# Wordwatch_-_complete.net
KiCad netlist of a schematic drawn in EAGLE
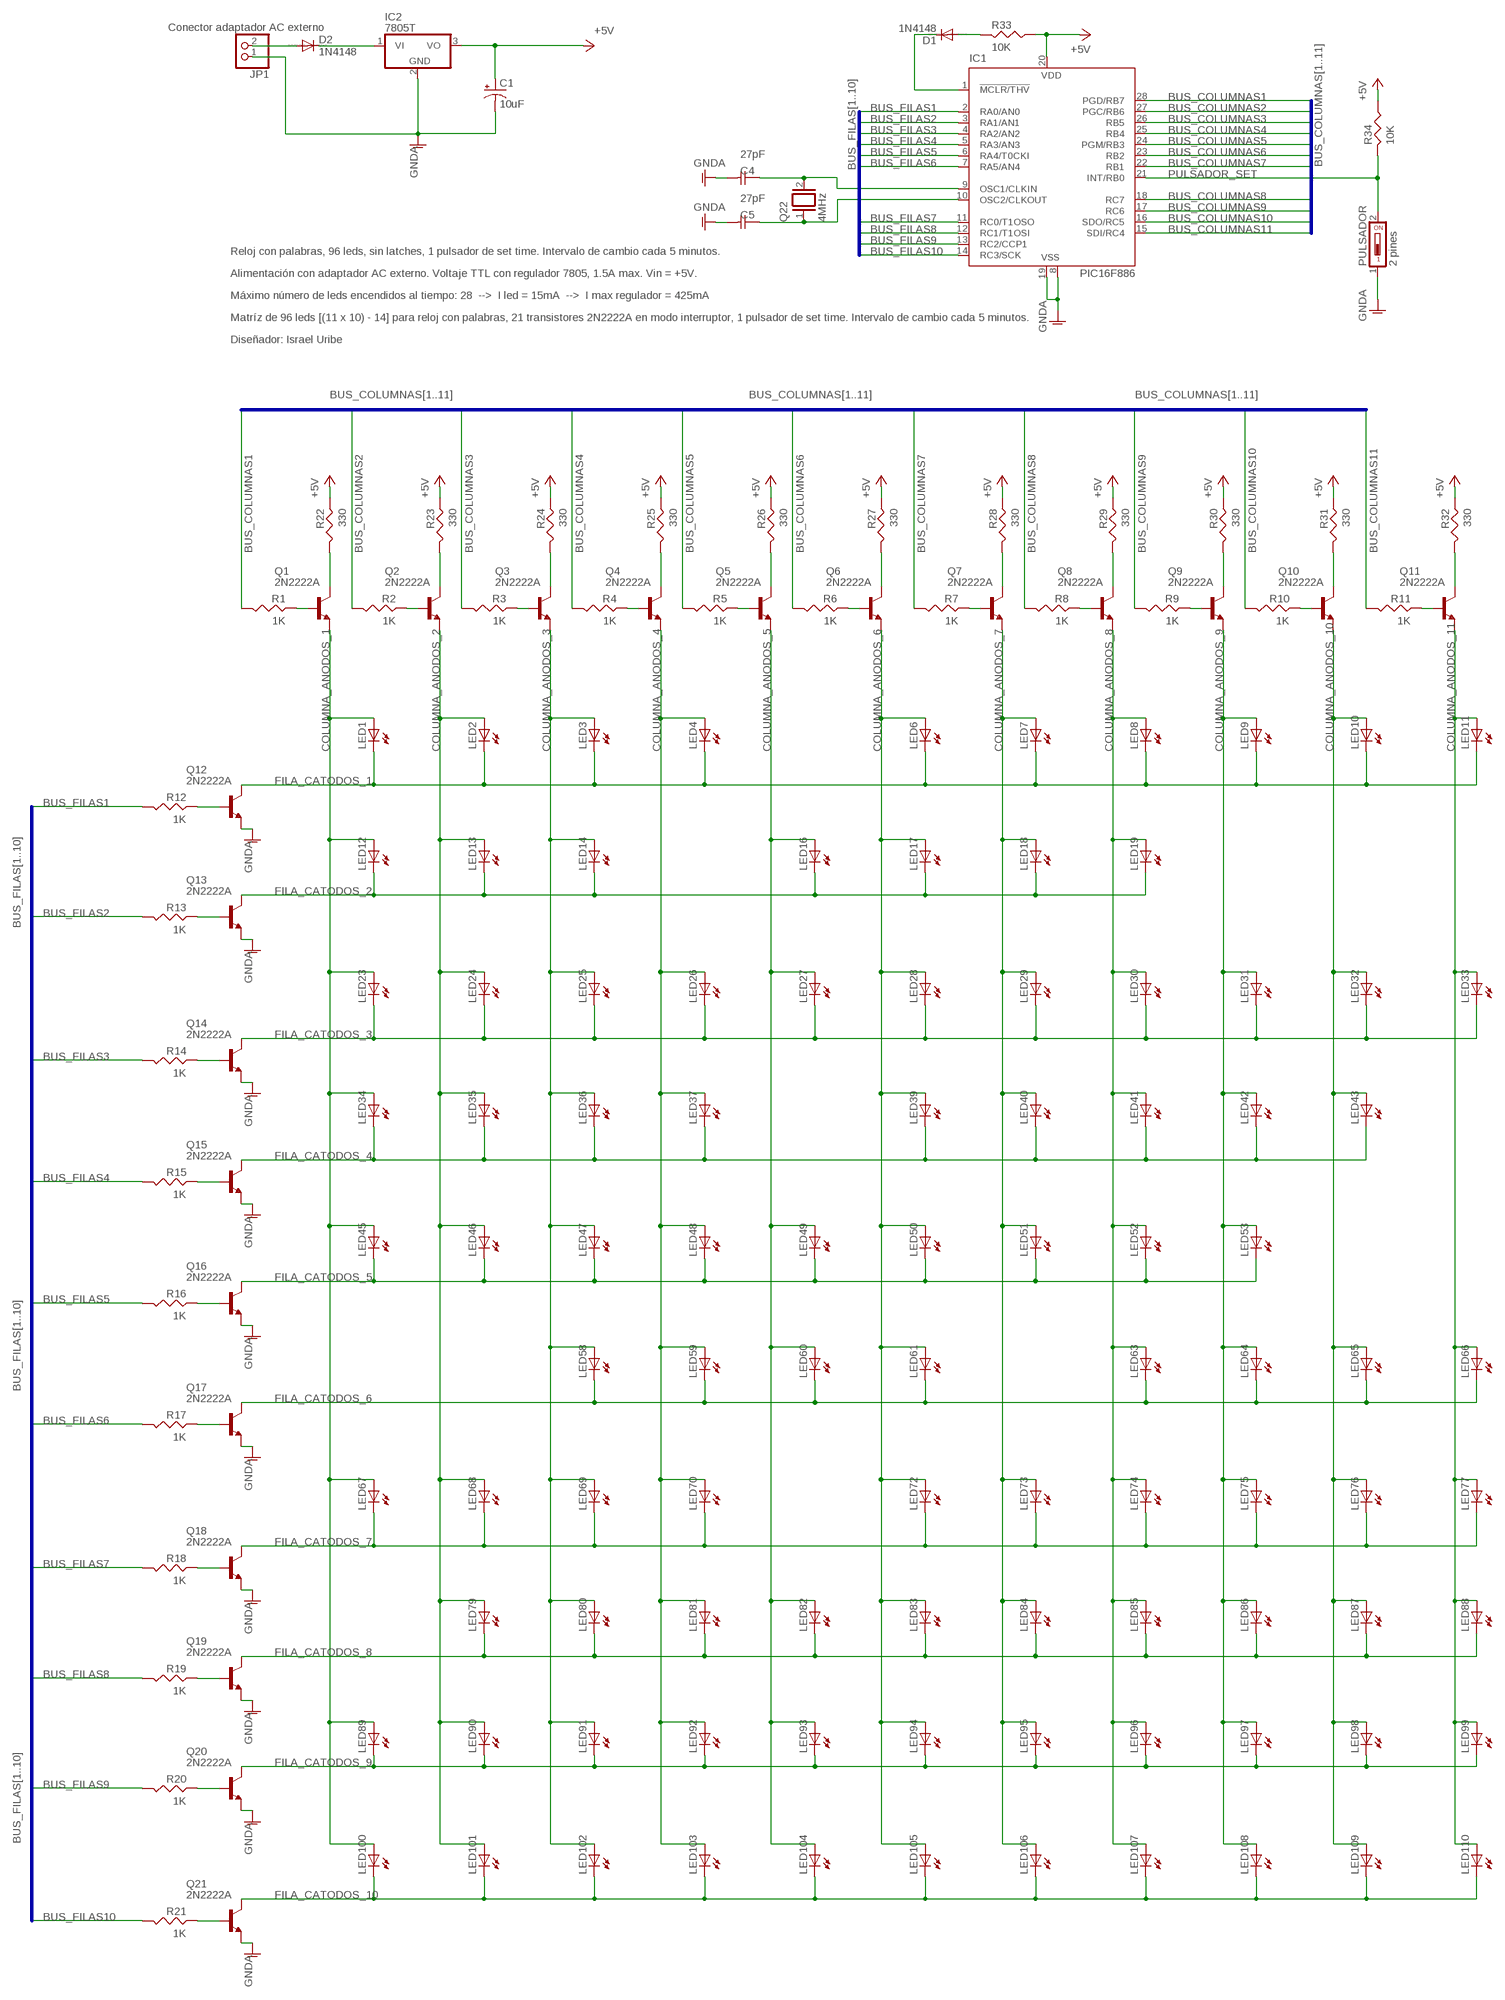
[diagram p0: schematic, sheet 1]

(export (version "E")
  (design (tool "Eeschema 10.0.6"))
  (components
    (comp (ref "C1")
      (value "10uF")
      (footprint "eagle-import:E2-4")
      (libsource (lib "eagle-import") (part "CPOL-USE2-4"))
    )
    (comp (ref "C4")
      (value "27pF")
      (footprint "eagle-import:C-2,5")
      (libsource (lib "eagle-import") (part "CAPNP-2,5"))
    )
    (comp (ref "C5")
      (value "27pF")
      (footprint "eagle-import:C-2,5")
      (libsource (lib "eagle-import") (part "CAPNP-2,5"))
    )
    (comp (ref "D1")
      (value "1N4148")
      (footprint "eagle-import:D-7.5")
      (libsource (lib "eagle-import") (part "DIODE-D-7.5"))
    )
    (comp (ref "D2")
      (value "1N4148")
      (footprint "eagle-import:D-7.5")
      (libsource (lib "eagle-import") (part "DIODE-D-7.5"))
    )
    (comp (ref "IC1")
      (value "PIC16F886")
      (footprint "eagle-import:DIL28-3")
      (libsource (lib "eagle-import") (part "PIC16876P"))
    )
    (comp (ref "IC2")
      (value "7805T")
      (footprint "eagle-import:TO220H")
      (libsource (lib "eagle-import") (part "78T05"))
    )
    (comp (ref "JP1")
      (value "Conector adaptador AC externo")
      (footprint "eagle-import:1X02")
      (libsource (lib "eagle-import") (part "PINHD-1X2"))
    )
    (comp (ref "LED1")
      (value "LED3MM")
      (footprint "eagle-import:LED3MM")
      (libsource (lib "eagle-import") (part "LED3MM"))
    )
    (comp (ref "LED2")
      (value "LED3MM")
      (footprint "eagle-import:LED3MM")
      (libsource (lib "eagle-import") (part "LED3MM"))
    )
    (comp (ref "LED3")
      (value "LED3MM")
      (footprint "eagle-import:LED3MM")
      (libsource (lib "eagle-import") (part "LED3MM"))
    )
    (comp (ref "LED4")
      (value "LED3MM")
      (footprint "eagle-import:LED3MM")
      (libsource (lib "eagle-import") (part "LED3MM"))
    )
    (comp (ref "LED6")
      (value "LED3MM")
      (footprint "eagle-import:LED3MM")
      (libsource (lib "eagle-import") (part "LED3MM"))
    )
    (comp (ref "LED7")
      (value "LED3MM")
      (footprint "eagle-import:LED3MM")
      (libsource (lib "eagle-import") (part "LED3MM"))
    )
    (comp (ref "LED8")
      (value "LED3MM")
      (footprint "eagle-import:LED3MM")
      (libsource (lib "eagle-import") (part "LED3MM"))
    )
    (comp (ref "LED9")
      (value "LED3MM")
      (footprint "eagle-import:LED3MM")
      (libsource (lib "eagle-import") (part "LED3MM"))
    )
    (comp (ref "LED10")
      (value "LED3MM")
      (footprint "eagle-import:LED3MM")
      (libsource (lib "eagle-import") (part "LED3MM"))
    )
    (comp (ref "LED11")
      (value "LED3MM")
      (footprint "eagle-import:LED3MM")
      (libsource (lib "eagle-import") (part "LED3MM"))
    )
    (comp (ref "LED12")
      (value "LED3MM")
      (footprint "eagle-import:LED3MM")
      (libsource (lib "eagle-import") (part "LED3MM"))
    )
    (comp (ref "LED13")
      (value "LED3MM")
      (footprint "eagle-import:LED3MM")
      (libsource (lib "eagle-import") (part "LED3MM"))
    )
    (comp (ref "LED14")
      (value "LED3MM")
      (footprint "eagle-import:LED3MM")
      (libsource (lib "eagle-import") (part "LED3MM"))
    )
    (comp (ref "LED16")
      (value "LED3MM")
      (footprint "eagle-import:LED3MM")
      (libsource (lib "eagle-import") (part "LED3MM"))
    )
    (comp (ref "LED17")
      (value "LED3MM")
      (footprint "eagle-import:LED3MM")
      (libsource (lib "eagle-import") (part "LED3MM"))
    )
    (comp (ref "LED18")
      (value "LED3MM")
      (footprint "eagle-import:LED3MM")
      (libsource (lib "eagle-import") (part "LED3MM"))
    )
    (comp (ref "LED19")
      (value "LED3MM")
      (footprint "eagle-import:LED3MM")
      (libsource (lib "eagle-import") (part "LED3MM"))
    )
    (comp (ref "LED23")
      (value "LED3MM")
      (footprint "eagle-import:LED3MM")
      (libsource (lib "eagle-import") (part "LED3MM"))
    )
    (comp (ref "LED24")
      (value "LED3MM")
      (footprint "eagle-import:LED3MM")
      (libsource (lib "eagle-import") (part "LED3MM"))
    )
    (comp (ref "LED25")
      (value "LED3MM")
      (footprint "eagle-import:LED3MM")
      (libsource (lib "eagle-import") (part "LED3MM"))
    )
    (comp (ref "LED26")
      (value "LED3MM")
      (footprint "eagle-import:LED3MM")
      (libsource (lib "eagle-import") (part "LED3MM"))
    )
    (comp (ref "LED27")
      (value "LED3MM")
      (footprint "eagle-import:LED3MM")
      (libsource (lib "eagle-import") (part "LED3MM"))
    )
    (comp (ref "LED28")
      (value "LED3MM")
      (footprint "eagle-import:LED3MM")
      (libsource (lib "eagle-import") (part "LED3MM"))
    )
    (comp (ref "LED29")
      (value "LED3MM")
      (footprint "eagle-import:LED3MM")
      (libsource (lib "eagle-import") (part "LED3MM"))
    )
    (comp (ref "LED30")
      (value "LED3MM")
      (footprint "eagle-import:LED3MM")
      (libsource (lib "eagle-import") (part "LED3MM"))
    )
    (comp (ref "LED31")
      (value "LED3MM")
      (footprint "eagle-import:LED3MM")
      (libsource (lib "eagle-import") (part "LED3MM"))
    )
    (comp (ref "LED32")
      (value "LED3MM")
      (footprint "eagle-import:LED3MM")
      (libsource (lib "eagle-import") (part "LED3MM"))
    )
    (comp (ref "LED33")
      (value "LED3MM")
      (footprint "eagle-import:LED3MM")
      (libsource (lib "eagle-import") (part "LED3MM"))
    )
    (comp (ref "LED34")
      (value "LED3MM")
      (footprint "eagle-import:LED3MM")
      (libsource (lib "eagle-import") (part "LED3MM"))
    )
    (comp (ref "LED35")
      (value "LED3MM")
      (footprint "eagle-import:LED3MM")
      (libsource (lib "eagle-import") (part "LED3MM"))
    )
    (comp (ref "LED36")
      (value "LED3MM")
      (footprint "eagle-import:LED3MM")
      (libsource (lib "eagle-import") (part "LED3MM"))
    )
    (comp (ref "LED37")
      (value "LED3MM")
      (footprint "eagle-import:LED3MM")
      (libsource (lib "eagle-import") (part "LED3MM"))
    )
    (comp (ref "LED39")
      (value "LED3MM")
      (footprint "eagle-import:LED3MM")
      (libsource (lib "eagle-import") (part "LED3MM"))
    )
    (comp (ref "LED40")
      (value "LED3MM")
      (footprint "eagle-import:LED3MM")
      (libsource (lib "eagle-import") (part "LED3MM"))
    )
    (comp (ref "LED41")
      (value "LED3MM")
      (footprint "eagle-import:LED3MM")
      (libsource (lib "eagle-import") (part "LED3MM"))
    )
    (comp (ref "LED42")
      (value "LED3MM")
      (footprint "eagle-import:LED3MM")
      (libsource (lib "eagle-import") (part "LED3MM"))
    )
    (comp (ref "LED43")
      (value "LED3MM")
      (footprint "eagle-import:LED3MM")
      (libsource (lib "eagle-import") (part "LED3MM"))
    )
    (comp (ref "LED45")
      (value "LED3MM")
      (footprint "eagle-import:LED3MM")
      (libsource (lib "eagle-import") (part "LED3MM"))
    )
    (comp (ref "LED46")
      (value "LED3MM")
      (footprint "eagle-import:LED3MM")
      (libsource (lib "eagle-import") (part "LED3MM"))
    )
    (comp (ref "LED47")
      (value "LED3MM")
      (footprint "eagle-import:LED3MM")
      (libsource (lib "eagle-import") (part "LED3MM"))
    )
    (comp (ref "LED48")
      (value "LED3MM")
      (footprint "eagle-import:LED3MM")
      (libsource (lib "eagle-import") (part "LED3MM"))
    )
    (comp (ref "LED49")
      (value "LED3MM")
      (footprint "eagle-import:LED3MM")
      (libsource (lib "eagle-import") (part "LED3MM"))
    )
    (comp (ref "LED50")
      (value "LED3MM")
      (footprint "eagle-import:LED3MM")
      (libsource (lib "eagle-import") (part "LED3MM"))
    )
    (comp (ref "LED51")
      (value "LED3MM")
      (footprint "eagle-import:LED3MM")
      (libsource (lib "eagle-import") (part "LED3MM"))
    )
    (comp (ref "LED52")
      (value "LED3MM")
      (footprint "eagle-import:LED3MM")
      (libsource (lib "eagle-import") (part "LED3MM"))
    )
    (comp (ref "LED53")
      (value "LED3MM")
      (footprint "eagle-import:LED3MM")
      (libsource (lib "eagle-import") (part "LED3MM"))
    )
    (comp (ref "LED58")
      (value "LED3MM")
      (footprint "eagle-import:LED3MM")
      (libsource (lib "eagle-import") (part "LED3MM"))
    )
    (comp (ref "LED59")
      (value "LED3MM")
      (footprint "eagle-import:LED3MM")
      (libsource (lib "eagle-import") (part "LED3MM"))
    )
    (comp (ref "LED60")
      (value "LED3MM")
      (footprint "eagle-import:LED3MM")
      (libsource (lib "eagle-import") (part "LED3MM"))
    )
    (comp (ref "LED61")
      (value "LED3MM")
      (footprint "eagle-import:LED3MM")
      (libsource (lib "eagle-import") (part "LED3MM"))
    )
    (comp (ref "LED63")
      (value "LED3MM")
      (footprint "eagle-import:LED3MM")
      (libsource (lib "eagle-import") (part "LED3MM"))
    )
    (comp (ref "LED64")
      (value "LED3MM")
      (footprint "eagle-import:LED3MM")
      (libsource (lib "eagle-import") (part "LED3MM"))
    )
    (comp (ref "LED65")
      (value "LED3MM")
      (footprint "eagle-import:LED3MM")
      (libsource (lib "eagle-import") (part "LED3MM"))
    )
    (comp (ref "LED66")
      (value "LED3MM")
      (footprint "eagle-import:LED3MM")
      (libsource (lib "eagle-import") (part "LED3MM"))
    )
    (comp (ref "LED67")
      (value "LED3MM")
      (footprint "eagle-import:LED3MM")
      (libsource (lib "eagle-import") (part "LED3MM"))
    )
    (comp (ref "LED68")
      (value "LED3MM")
      (footprint "eagle-import:LED3MM")
      (libsource (lib "eagle-import") (part "LED3MM"))
    )
    (comp (ref "LED69")
      (value "LED3MM")
      (footprint "eagle-import:LED3MM")
      (libsource (lib "eagle-import") (part "LED3MM"))
    )
    (comp (ref "LED70")
      (value "LED3MM")
      (footprint "eagle-import:LED3MM")
      (libsource (lib "eagle-import") (part "LED3MM"))
    )
    (comp (ref "LED72")
      (value "LED3MM")
      (footprint "eagle-import:LED3MM")
      (libsource (lib "eagle-import") (part "LED3MM"))
    )
    (comp (ref "LED73")
      (value "LED3MM")
      (footprint "eagle-import:LED3MM")
      (libsource (lib "eagle-import") (part "LED3MM"))
    )
    (comp (ref "LED74")
      (value "LED3MM")
      (footprint "eagle-import:LED3MM")
      (libsource (lib "eagle-import") (part "LED3MM"))
    )
    (comp (ref "LED75")
      (value "LED3MM")
      (footprint "eagle-import:LED3MM")
      (libsource (lib "eagle-import") (part "LED3MM"))
    )
    (comp (ref "LED76")
      (value "LED3MM")
      (footprint "eagle-import:LED3MM")
      (libsource (lib "eagle-import") (part "LED3MM"))
    )
    (comp (ref "LED77")
      (value "LED3MM")
      (footprint "eagle-import:LED3MM")
      (libsource (lib "eagle-import") (part "LED3MM"))
    )
    (comp (ref "LED79")
      (value "LED3MM")
      (footprint "eagle-import:LED3MM")
      (libsource (lib "eagle-import") (part "LED3MM"))
    )
    (comp (ref "LED80")
      (value "LED3MM")
      (footprint "eagle-import:LED3MM")
      (libsource (lib "eagle-import") (part "LED3MM"))
    )
    (comp (ref "LED81")
      (value "LED3MM")
      (footprint "eagle-import:LED3MM")
      (libsource (lib "eagle-import") (part "LED3MM"))
    )
    (comp (ref "LED82")
      (value "LED3MM")
      (footprint "eagle-import:LED3MM")
      (libsource (lib "eagle-import") (part "LED3MM"))
    )
    (comp (ref "LED83")
      (value "LED3MM")
      (footprint "eagle-import:LED3MM")
      (libsource (lib "eagle-import") (part "LED3MM"))
    )
    (comp (ref "LED84")
      (value "LED3MM")
      (footprint "eagle-import:LED3MM")
      (libsource (lib "eagle-import") (part "LED3MM"))
    )
    (comp (ref "LED85")
      (value "LED3MM")
      (footprint "eagle-import:LED3MM")
      (libsource (lib "eagle-import") (part "LED3MM"))
    )
    (comp (ref "LED86")
      (value "LED3MM")
      (footprint "eagle-import:LED3MM")
      (libsource (lib "eagle-import") (part "LED3MM"))
    )
    (comp (ref "LED87")
      (value "LED3MM")
      (footprint "eagle-import:LED3MM")
      (libsource (lib "eagle-import") (part "LED3MM"))
    )
    (comp (ref "LED88")
      (value "LED3MM")
      (footprint "eagle-import:LED3MM")
      (libsource (lib "eagle-import") (part "LED3MM"))
    )
    (comp (ref "LED89")
      (value "LED3MM")
      (footprint "eagle-import:LED3MM")
      (libsource (lib "eagle-import") (part "LED3MM"))
    )
    (comp (ref "LED90")
      (value "LED3MM")
      (footprint "eagle-import:LED3MM")
      (libsource (lib "eagle-import") (part "LED3MM"))
    )
    (comp (ref "LED91")
      (value "LED3MM")
      (footprint "eagle-import:LED3MM")
      (libsource (lib "eagle-import") (part "LED3MM"))
    )
    (comp (ref "LED92")
      (value "LED3MM")
      (footprint "eagle-import:LED3MM")
      (libsource (lib "eagle-import") (part "LED3MM"))
    )
    (comp (ref "LED93")
      (value "LED3MM")
      (footprint "eagle-import:LED3MM")
      (libsource (lib "eagle-import") (part "LED3MM"))
    )
    (comp (ref "LED94")
      (value "LED3MM")
      (footprint "eagle-import:LED3MM")
      (libsource (lib "eagle-import") (part "LED3MM"))
    )
    (comp (ref "LED95")
      (value "LED3MM")
      (footprint "eagle-import:LED3MM")
      (libsource (lib "eagle-import") (part "LED3MM"))
    )
    (comp (ref "LED96")
      (value "LED3MM")
      (footprint "eagle-import:LED3MM")
      (libsource (lib "eagle-import") (part "LED3MM"))
    )
    (comp (ref "LED97")
      (value "LED3MM")
      (footprint "eagle-import:LED3MM")
      (libsource (lib "eagle-import") (part "LED3MM"))
    )
    (comp (ref "LED98")
      (value "LED3MM")
      (footprint "eagle-import:LED3MM")
      (libsource (lib "eagle-import") (part "LED3MM"))
    )
    (comp (ref "LED99")
      (value "LED3MM")
      (footprint "eagle-import:LED3MM")
      (libsource (lib "eagle-import") (part "LED3MM"))
    )
    (comp (ref "LED100")
      (value "LED3MM")
      (footprint "eagle-import:LED3MM")
      (libsource (lib "eagle-import") (part "LED3MM"))
    )
    (comp (ref "LED101")
      (value "LED3MM")
      (footprint "eagle-import:LED3MM")
      (libsource (lib "eagle-import") (part "LED3MM"))
    )
    (comp (ref "LED102")
      (value "LED3MM")
      (footprint "eagle-import:LED3MM")
      (libsource (lib "eagle-import") (part "LED3MM"))
    )
    (comp (ref "LED103")
      (value "LED3MM")
      (footprint "eagle-import:LED3MM")
      (libsource (lib "eagle-import") (part "LED3MM"))
    )
    (comp (ref "LED104")
      (value "LED3MM")
      (footprint "eagle-import:LED3MM")
      (libsource (lib "eagle-import") (part "LED3MM"))
    )
    (comp (ref "LED105")
      (value "LED3MM")
      (footprint "eagle-import:LED3MM")
      (libsource (lib "eagle-import") (part "LED3MM"))
    )
    (comp (ref "LED106")
      (value "LED3MM")
      (footprint "eagle-import:LED3MM")
      (libsource (lib "eagle-import") (part "LED3MM"))
    )
    (comp (ref "LED107")
      (value "LED3MM")
      (footprint "eagle-import:LED3MM")
      (libsource (lib "eagle-import") (part "LED3MM"))
    )
    (comp (ref "LED108")
      (value "LED3MM")
      (footprint "eagle-import:LED3MM")
      (libsource (lib "eagle-import") (part "LED3MM"))
    )
    (comp (ref "LED109")
      (value "LED3MM")
      (footprint "eagle-import:LED3MM")
      (libsource (lib "eagle-import") (part "LED3MM"))
    )
    (comp (ref "LED110")
      (value "LED3MM")
      (footprint "eagle-import:LED3MM")
      (libsource (lib "eagle-import") (part "LED3MM"))
    )
    (comp (ref "PULSADOR")
      (value "2 pines")
      (footprint "eagle-import:DS-01")
      (libsource (lib "eagle-import") (part "DS01"))
    )
    (comp (ref "Q1")
      (value "2N2222A")
      (footprint "eagle-import:TO92-CBE")
      (libsource (lib "eagle-import") (part "-NPN-TO92-CBE2N4124"))
    )
    (comp (ref "Q2")
      (value "2N2222A")
      (footprint "eagle-import:TO92-CBE")
      (libsource (lib "eagle-import") (part "-NPN-TO92-CBE2N4124"))
    )
    (comp (ref "Q3")
      (value "2N2222A")
      (footprint "eagle-import:TO92-CBE")
      (libsource (lib "eagle-import") (part "-NPN-TO92-CBE2N4124"))
    )
    (comp (ref "Q4")
      (value "2N2222A")
      (footprint "eagle-import:TO92-CBE")
      (libsource (lib "eagle-import") (part "-NPN-TO92-CBE2N4124"))
    )
    (comp (ref "Q5")
      (value "2N2222A")
      (footprint "eagle-import:TO92-CBE")
      (libsource (lib "eagle-import") (part "-NPN-TO92-CBE2N4124"))
    )
    (comp (ref "Q6")
      (value "2N2222A")
      (footprint "eagle-import:TO92-CBE")
      (libsource (lib "eagle-import") (part "-NPN-TO92-CBE2N4124"))
    )
    (comp (ref "Q7")
      (value "2N2222A")
      (footprint "eagle-import:TO92-CBE")
      (libsource (lib "eagle-import") (part "-NPN-TO92-CBE2N4124"))
    )
    (comp (ref "Q8")
      (value "2N2222A")
      (footprint "eagle-import:TO92-CBE")
      (libsource (lib "eagle-import") (part "-NPN-TO92-CBE2N4124"))
    )
    (comp (ref "Q9")
      (value "2N2222A")
      (footprint "eagle-import:TO92-CBE")
      (libsource (lib "eagle-import") (part "-NPN-TO92-CBE2N4124"))
    )
    (comp (ref "Q10")
      (value "2N2222A")
      (footprint "eagle-import:TO92-CBE")
      (libsource (lib "eagle-import") (part "-NPN-TO92-CBE2N4124"))
    )
    (comp (ref "Q11")
      (value "2N2222A")
      (footprint "eagle-import:TO92-CBE")
      (libsource (lib "eagle-import") (part "-NPN-TO92-CBE2N4124"))
    )
    (comp (ref "Q12")
      (value "2N2222A")
      (footprint "eagle-import:TO92-CBE")
      (libsource (lib "eagle-import") (part "-NPN-TO92-CBE2N4124"))
    )
    (comp (ref "Q13")
      (value "2N2222A")
      (footprint "eagle-import:TO92-CBE")
      (libsource (lib "eagle-import") (part "-NPN-TO92-CBE2N4124"))
    )
    (comp (ref "Q14")
      (value "2N2222A")
      (footprint "eagle-import:TO92-CBE")
      (libsource (lib "eagle-import") (part "-NPN-TO92-CBE2N4124"))
    )
    (comp (ref "Q15")
      (value "2N2222A")
      (footprint "eagle-import:TO92-CBE")
      (libsource (lib "eagle-import") (part "-NPN-TO92-CBE2N4124"))
    )
    (comp (ref "Q16")
      (value "2N2222A")
      (footprint "eagle-import:TO92-CBE")
      (libsource (lib "eagle-import") (part "-NPN-TO92-CBE2N4124"))
    )
    (comp (ref "Q17")
      (value "2N2222A")
      (footprint "eagle-import:TO92-CBE")
      (libsource (lib "eagle-import") (part "-NPN-TO92-CBE2N4124"))
    )
    (comp (ref "Q18")
      (value "2N2222A")
      (footprint "eagle-import:TO92-CBE")
      (libsource (lib "eagle-import") (part "-NPN-TO92-CBE2N4124"))
    )
    (comp (ref "Q19")
      (value "2N2222A")
      (footprint "eagle-import:TO92-CBE")
      (libsource (lib "eagle-import") (part "-NPN-TO92-CBE2N4124"))
    )
    (comp (ref "Q20")
      (value "2N2222A")
      (footprint "eagle-import:TO92-CBE")
      (libsource (lib "eagle-import") (part "-NPN-TO92-CBE2N4124"))
    )
    (comp (ref "Q21")
      (value "2N2222A")
      (footprint "eagle-import:TO92-CBE")
      (libsource (lib "eagle-import") (part "-NPN-TO92-CBE2N4124"))
    )
    (comp (ref "Q22")
      (value "4MHz")
      (footprint "eagle-import:QS")
      (libsource (lib "eagle-import") (part "XTAL/S"))
    )
    (comp (ref "R1")
      (value "1K")
      (footprint "eagle-import:R-5")
      (libsource (lib "eagle-import") (part "RESUS-5"))
    )
    (comp (ref "R2")
      (value "1K")
      (footprint "eagle-import:R-5")
      (libsource (lib "eagle-import") (part "RESUS-5"))
    )
    (comp (ref "R3")
      (value "1K")
      (footprint "eagle-import:R-5")
      (libsource (lib "eagle-import") (part "RESUS-5"))
    )
    (comp (ref "R4")
      (value "1K")
      (footprint "eagle-import:R-5")
      (libsource (lib "eagle-import") (part "RESUS-5"))
    )
    (comp (ref "R5")
      (value "1K")
      (footprint "eagle-import:R-5")
      (libsource (lib "eagle-import") (part "RESUS-5"))
    )
    (comp (ref "R6")
      (value "1K")
      (footprint "eagle-import:R-5")
      (libsource (lib "eagle-import") (part "RESUS-5"))
    )
    (comp (ref "R7")
      (value "1K")
      (footprint "eagle-import:R-5")
      (libsource (lib "eagle-import") (part "RESUS-5"))
    )
    (comp (ref "R8")
      (value "1K")
      (footprint "eagle-import:R-5")
      (libsource (lib "eagle-import") (part "RESUS-5"))
    )
    (comp (ref "R9")
      (value "1K")
      (footprint "eagle-import:R-5")
      (libsource (lib "eagle-import") (part "RESUS-5"))
    )
    (comp (ref "R10")
      (value "1K")
      (footprint "eagle-import:R-5")
      (libsource (lib "eagle-import") (part "RESUS-5"))
    )
    (comp (ref "R11")
      (value "1K")
      (footprint "eagle-import:R-5")
      (libsource (lib "eagle-import") (part "RESUS-5"))
    )
    (comp (ref "R12")
      (value "1K")
      (footprint "eagle-import:R-5")
      (libsource (lib "eagle-import") (part "RESUS-5"))
    )
    (comp (ref "R13")
      (value "1K")
      (footprint "eagle-import:R-5")
      (libsource (lib "eagle-import") (part "RESUS-5"))
    )
    (comp (ref "R14")
      (value "1K")
      (footprint "eagle-import:R-5")
      (libsource (lib "eagle-import") (part "RESUS-5"))
    )
    (comp (ref "R15")
      (value "1K")
      (footprint "eagle-import:R-5")
      (libsource (lib "eagle-import") (part "RESUS-5"))
    )
    (comp (ref "R16")
      (value "1K")
      (footprint "eagle-import:R-5")
      (libsource (lib "eagle-import") (part "RESUS-5"))
    )
    (comp (ref "R17")
      (value "1K")
      (footprint "eagle-import:R-5")
      (libsource (lib "eagle-import") (part "RESUS-5"))
    )
    (comp (ref "R18")
      (value "1K")
      (footprint "eagle-import:R-5")
      (libsource (lib "eagle-import") (part "RESUS-5"))
    )
    (comp (ref "R19")
      (value "1K")
      (footprint "eagle-import:R-5")
      (libsource (lib "eagle-import") (part "RESUS-5"))
    )
    (comp (ref "R20")
      (value "1K")
      (footprint "eagle-import:R-5")
      (libsource (lib "eagle-import") (part "RESUS-5"))
    )
    (comp (ref "R21")
      (value "1K")
      (footprint "eagle-import:R-5")
      (libsource (lib "eagle-import") (part "RESUS-5"))
    )
    (comp (ref "R22")
      (value "330")
      (footprint "eagle-import:R-5")
      (libsource (lib "eagle-import") (part "RESUS-5"))
    )
    (comp (ref "R23")
      (value "330")
      (footprint "eagle-import:R-5")
      (libsource (lib "eagle-import") (part "RESUS-5"))
    )
    (comp (ref "R24")
      (value "330")
      (footprint "eagle-import:R-5")
      (libsource (lib "eagle-import") (part "RESUS-5"))
    )
    (comp (ref "R25")
      (value "330")
      (footprint "eagle-import:R-5")
      (libsource (lib "eagle-import") (part "RESUS-5"))
    )
    (comp (ref "R26")
      (value "330")
      (footprint "eagle-import:R-5")
      (libsource (lib "eagle-import") (part "RESUS-5"))
    )
    (comp (ref "R27")
      (value "330")
      (footprint "eagle-import:R-5")
      (libsource (lib "eagle-import") (part "RESUS-5"))
    )
    (comp (ref "R28")
      (value "330")
      (footprint "eagle-import:R-5")
      (libsource (lib "eagle-import") (part "RESUS-5"))
    )
    (comp (ref "R29")
      (value "330")
      (footprint "eagle-import:R-5")
      (libsource (lib "eagle-import") (part "RESUS-5"))
    )
    (comp (ref "R30")
      (value "330")
      (footprint "eagle-import:R-5")
      (libsource (lib "eagle-import") (part "RESUS-5"))
    )
    (comp (ref "R31")
      (value "330")
      (footprint "eagle-import:R-5")
      (libsource (lib "eagle-import") (part "RESUS-5"))
    )
    (comp (ref "R32")
      (value "330")
      (footprint "eagle-import:R-5")
      (libsource (lib "eagle-import") (part "RESUS-5"))
    )
    (comp (ref "R33")
      (value "10K")
      (footprint "eagle-import:R-5")
      (libsource (lib "eagle-import") (part "RESUS-5"))
    )
    (comp (ref "R34")
      (value "10K")
      (footprint "eagle-import:R-5")
      (libsource (lib "eagle-import") (part "RESUS-5"))
    )
  )
  (nets
    (net (code "1") (name "+5V") (class "Default")
      (node (ref "C1") (pin "+") (pinfunction "+_+") (pintype "passive"))
      (node (ref "IC1") (pin "20") (pinfunction "VDD_20") (pintype "power_in"))
      (node (ref "IC2") (pin "3") (pinfunction "VO_3") (pintype "passive"))
      (node (ref "R22") (pin "2") (pinfunction "2_2") (pintype "passive"))
      (node (ref "R23") (pin "2") (pinfunction "2_2") (pintype "passive"))
      (node (ref "R24") (pin "2") (pinfunction "2_2") (pintype "passive"))
      (node (ref "R25") (pin "2") (pinfunction "2_2") (pintype "passive"))
      (node (ref "R26") (pin "2") (pinfunction "2_2") (pintype "passive"))
      (node (ref "R27") (pin "2") (pinfunction "2_2") (pintype "passive"))
      (node (ref "R28") (pin "2") (pinfunction "2_2") (pintype "passive"))
      (node (ref "R29") (pin "2") (pinfunction "2_2") (pintype "passive"))
      (node (ref "R30") (pin "2") (pinfunction "2_2") (pintype "passive"))
      (node (ref "R31") (pin "2") (pinfunction "2_2") (pintype "passive"))
      (node (ref "R32") (pin "2") (pinfunction "2_2") (pintype "passive"))
      (node (ref "R33") (pin "1") (pinfunction "1_1") (pintype "passive"))
      (node (ref "R34") (pin "1") (pinfunction "1_1") (pintype "passive"))
    )
    (net (code "2") (name "/BUS_COLUMNAS1") (class "Default")
      (node (ref "IC1") (pin "28") (pinfunction "PGD/RB7_28") (pintype "bidirectional"))
      (node (ref "R1") (pin "1") (pinfunction "1_1") (pintype "passive"))
    )
    (net (code "3") (name "/BUS_COLUMNAS2") (class "Default")
      (node (ref "IC1") (pin "27") (pinfunction "PGC/RB6_27") (pintype "bidirectional"))
      (node (ref "R2") (pin "1") (pinfunction "1_1") (pintype "passive"))
    )
    (net (code "4") (name "/BUS_COLUMNAS3") (class "Default")
      (node (ref "IC1") (pin "26") (pinfunction "RB5_26") (pintype "bidirectional"))
      (node (ref "R3") (pin "1") (pinfunction "1_1") (pintype "passive"))
    )
    (net (code "5") (name "/BUS_COLUMNAS4") (class "Default")
      (node (ref "IC1") (pin "25") (pinfunction "RB4_25") (pintype "bidirectional"))
      (node (ref "R4") (pin "1") (pinfunction "1_1") (pintype "passive"))
    )
    (net (code "6") (name "/BUS_COLUMNAS5") (class "Default")
      (node (ref "IC1") (pin "24") (pinfunction "PGM/RB3_24") (pintype "bidirectional"))
      (node (ref "R5") (pin "1") (pinfunction "1_1") (pintype "passive"))
    )
    (net (code "7") (name "/BUS_COLUMNAS6") (class "Default")
      (node (ref "IC1") (pin "23") (pinfunction "RB2_23") (pintype "bidirectional"))
      (node (ref "R6") (pin "1") (pinfunction "1_1") (pintype "passive"))
    )
    (net (code "8") (name "/BUS_COLUMNAS7") (class "Default")
      (node (ref "IC1") (pin "22") (pinfunction "RB1_22") (pintype "bidirectional"))
      (node (ref "R7") (pin "1") (pinfunction "1_1") (pintype "passive"))
    )
    (net (code "9") (name "/BUS_COLUMNAS8") (class "Default")
      (node (ref "IC1") (pin "18") (pinfunction "RC7_18") (pintype "bidirectional"))
      (node (ref "R8") (pin "1") (pinfunction "1_1") (pintype "passive"))
    )
    (net (code "10") (name "/BUS_COLUMNAS9") (class "Default")
      (node (ref "IC1") (pin "17") (pinfunction "RC6_17") (pintype "bidirectional"))
      (node (ref "R9") (pin "1") (pinfunction "1_1") (pintype "passive"))
    )
    (net (code "11") (name "/BUS_COLUMNAS10") (class "Default")
      (node (ref "IC1") (pin "16") (pinfunction "SDO/RC5_16") (pintype "bidirectional"))
      (node (ref "R10") (pin "1") (pinfunction "1_1") (pintype "passive"))
    )
    (net (code "12") (name "/BUS_COLUMNAS11") (class "Default")
      (node (ref "IC1") (pin "15") (pinfunction "SDI/RC4_15") (pintype "bidirectional"))
      (node (ref "R11") (pin "1") (pinfunction "1_1") (pintype "passive"))
    )
    (net (code "14") (name "/BUS_FILAS1") (class "Default")
      (node (ref "IC1") (pin "2") (pinfunction "RA0/AN0_2") (pintype "bidirectional"))
      (node (ref "R12") (pin "1") (pinfunction "1_1") (pintype "passive"))
    )
    (net (code "15") (name "/BUS_FILAS2") (class "Default")
      (node (ref "IC1") (pin "3") (pinfunction "RA1/AN1_3") (pintype "bidirectional"))
      (node (ref "R13") (pin "1") (pinfunction "1_1") (pintype "passive"))
    )
    (net (code "16") (name "/BUS_FILAS3") (class "Default")
      (node (ref "IC1") (pin "4") (pinfunction "RA2/AN2_4") (pintype "bidirectional"))
      (node (ref "R14") (pin "1") (pinfunction "1_1") (pintype "passive"))
    )
    (net (code "17") (name "/BUS_FILAS4") (class "Default")
      (node (ref "IC1") (pin "5") (pinfunction "RA3/AN3_5") (pintype "bidirectional"))
      (node (ref "R15") (pin "1") (pinfunction "1_1") (pintype "passive"))
    )
    (net (code "18") (name "/BUS_FILAS5") (class "Default")
      (node (ref "IC1") (pin "6") (pinfunction "RA4/T0CKI_6") (pintype "bidirectional"))
      (node (ref "R16") (pin "1") (pinfunction "1_1") (pintype "passive"))
    )
    (net (code "19") (name "/BUS_FILAS6") (class "Default")
      (node (ref "IC1") (pin "7") (pinfunction "RA5/AN4_7") (pintype "bidirectional"))
      (node (ref "R17") (pin "1") (pinfunction "1_1") (pintype "passive"))
    )
    (net (code "20") (name "/BUS_FILAS7") (class "Default")
      (node (ref "IC1") (pin "11") (pinfunction "RC0/T1OSO_11") (pintype "bidirectional"))
      (node (ref "R18") (pin "1") (pinfunction "1_1") (pintype "passive"))
    )
    (net (code "21") (name "/BUS_FILAS8") (class "Default")
      (node (ref "IC1") (pin "12") (pinfunction "RC1/T1OSI_12") (pintype "bidirectional"))
      (node (ref "R19") (pin "1") (pinfunction "1_1") (pintype "passive"))
    )
    (net (code "22") (name "/BUS_FILAS9") (class "Default")
      (node (ref "IC1") (pin "13") (pinfunction "RC2/CCP1_13") (pintype "bidirectional"))
      (node (ref "R20") (pin "1") (pinfunction "1_1") (pintype "passive"))
    )
    (net (code "23") (name "/BUS_FILAS10") (class "Default")
      (node (ref "IC1") (pin "14") (pinfunction "RC3/SCK_14") (pintype "bidirectional"))
      (node (ref "R21") (pin "1") (pinfunction "1_1") (pintype "passive"))
    )
    (net (code "25") (name "/COLUMNA_ANODOS_1") (class "Default")
      (node (ref "LED1") (pin "A") (pinfunction "A_A") (pintype "passive"))
      (node (ref "LED100") (pin "A") (pinfunction "A_A") (pintype "passive"))
      (node (ref "LED12") (pin "A") (pinfunction "A_A") (pintype "passive"))
      (node (ref "LED23") (pin "A") (pinfunction "A_A") (pintype "passive"))
      (node (ref "LED34") (pin "A") (pinfunction "A_A") (pintype "passive"))
      (node (ref "LED45") (pin "A") (pinfunction "A_A") (pintype "passive"))
      (node (ref "LED67") (pin "A") (pinfunction "A_A") (pintype "passive"))
      (node (ref "LED89") (pin "A") (pinfunction "A_A") (pintype "passive"))
      (node (ref "Q1") (pin "E") (pinfunction "E_E") (pintype "passive"))
    )
    (net (code "26") (name "/COLUMNA_ANODOS_2") (class "Default")
      (node (ref "LED101") (pin "A") (pinfunction "A_A") (pintype "passive"))
      (node (ref "LED13") (pin "A") (pinfunction "A_A") (pintype "passive"))
      (node (ref "LED2") (pin "A") (pinfunction "A_A") (pintype "passive"))
      (node (ref "LED24") (pin "A") (pinfunction "A_A") (pintype "passive"))
      (node (ref "LED35") (pin "A") (pinfunction "A_A") (pintype "passive"))
      (node (ref "LED46") (pin "A") (pinfunction "A_A") (pintype "passive"))
      (node (ref "LED68") (pin "A") (pinfunction "A_A") (pintype "passive"))
      (node (ref "LED79") (pin "A") (pinfunction "A_A") (pintype "passive"))
      (node (ref "LED90") (pin "A") (pinfunction "A_A") (pintype "passive"))
      (node (ref "Q2") (pin "E") (pinfunction "E_E") (pintype "passive"))
    )
    (net (code "27") (name "/COLUMNA_ANODOS_3") (class "Default")
      (node (ref "LED102") (pin "A") (pinfunction "A_A") (pintype "passive"))
      (node (ref "LED14") (pin "A") (pinfunction "A_A") (pintype "passive"))
      (node (ref "LED25") (pin "A") (pinfunction "A_A") (pintype "passive"))
      (node (ref "LED3") (pin "A") (pinfunction "A_A") (pintype "passive"))
      (node (ref "LED36") (pin "A") (pinfunction "A_A") (pintype "passive"))
      (node (ref "LED47") (pin "A") (pinfunction "A_A") (pintype "passive"))
      (node (ref "LED58") (pin "A") (pinfunction "A_A") (pintype "passive"))
      (node (ref "LED69") (pin "A") (pinfunction "A_A") (pintype "passive"))
      (node (ref "LED80") (pin "A") (pinfunction "A_A") (pintype "passive"))
      (node (ref "LED91") (pin "A") (pinfunction "A_A") (pintype "passive"))
      (node (ref "Q3") (pin "E") (pinfunction "E_E") (pintype "passive"))
    )
    (net (code "28") (name "/COLUMNA_ANODOS_4") (class "Default")
      (node (ref "LED103") (pin "A") (pinfunction "A_A") (pintype "passive"))
      (node (ref "LED26") (pin "A") (pinfunction "A_A") (pintype "passive"))
      (node (ref "LED37") (pin "A") (pinfunction "A_A") (pintype "passive"))
      (node (ref "LED4") (pin "A") (pinfunction "A_A") (pintype "passive"))
      (node (ref "LED48") (pin "A") (pinfunction "A_A") (pintype "passive"))
      (node (ref "LED59") (pin "A") (pinfunction "A_A") (pintype "passive"))
      (node (ref "LED70") (pin "A") (pinfunction "A_A") (pintype "passive"))
      (node (ref "LED81") (pin "A") (pinfunction "A_A") (pintype "passive"))
      (node (ref "LED92") (pin "A") (pinfunction "A_A") (pintype "passive"))
      (node (ref "Q4") (pin "E") (pinfunction "E_E") (pintype "passive"))
    )
    (net (code "29") (name "/COLUMNA_ANODOS_5") (class "Default")
      (node (ref "LED104") (pin "A") (pinfunction "A_A") (pintype "passive"))
      (node (ref "LED16") (pin "A") (pinfunction "A_A") (pintype "passive"))
      (node (ref "LED27") (pin "A") (pinfunction "A_A") (pintype "passive"))
      (node (ref "LED49") (pin "A") (pinfunction "A_A") (pintype "passive"))
      (node (ref "LED60") (pin "A") (pinfunction "A_A") (pintype "passive"))
      (node (ref "LED82") (pin "A") (pinfunction "A_A") (pintype "passive"))
      (node (ref "LED93") (pin "A") (pinfunction "A_A") (pintype "passive"))
      (node (ref "Q5") (pin "E") (pinfunction "E_E") (pintype "passive"))
    )
    (net (code "30") (name "/COLUMNA_ANODOS_6") (class "Default")
      (node (ref "LED105") (pin "A") (pinfunction "A_A") (pintype "passive"))
      (node (ref "LED17") (pin "A") (pinfunction "A_A") (pintype "passive"))
      (node (ref "LED28") (pin "A") (pinfunction "A_A") (pintype "passive"))
      (node (ref "LED39") (pin "A") (pinfunction "A_A") (pintype "passive"))
      (node (ref "LED50") (pin "A") (pinfunction "A_A") (pintype "passive"))
      (node (ref "LED6") (pin "A") (pinfunction "A_A") (pintype "passive"))
      (node (ref "LED61") (pin "A") (pinfunction "A_A") (pintype "passive"))
      (node (ref "LED72") (pin "A") (pinfunction "A_A") (pintype "passive"))
      (node (ref "LED83") (pin "A") (pinfunction "A_A") (pintype "passive"))
      (node (ref "LED94") (pin "A") (pinfunction "A_A") (pintype "passive"))
      (node (ref "Q6") (pin "E") (pinfunction "E_E") (pintype "passive"))
    )
    (net (code "31") (name "/COLUMNA_ANODOS_7") (class "Default")
      (node (ref "LED106") (pin "A") (pinfunction "A_A") (pintype "passive"))
      (node (ref "LED18") (pin "A") (pinfunction "A_A") (pintype "passive"))
      (node (ref "LED29") (pin "A") (pinfunction "A_A") (pintype "passive"))
      (node (ref "LED40") (pin "A") (pinfunction "A_A") (pintype "passive"))
      (node (ref "LED51") (pin "A") (pinfunction "A_A") (pintype "passive"))
      (node (ref "LED7") (pin "A") (pinfunction "A_A") (pintype "passive"))
      (node (ref "LED73") (pin "A") (pinfunction "A_A") (pintype "passive"))
      (node (ref "LED84") (pin "A") (pinfunction "A_A") (pintype "passive"))
      (node (ref "LED95") (pin "A") (pinfunction "A_A") (pintype "passive"))
      (node (ref "Q7") (pin "E") (pinfunction "E_E") (pintype "passive"))
    )
    (net (code "32") (name "/COLUMNA_ANODOS_8") (class "Default")
      (node (ref "LED107") (pin "A") (pinfunction "A_A") (pintype "passive"))
      (node (ref "LED19") (pin "A") (pinfunction "A_A") (pintype "passive"))
      (node (ref "LED30") (pin "A") (pinfunction "A_A") (pintype "passive"))
      (node (ref "LED41") (pin "A") (pinfunction "A_A") (pintype "passive"))
      (node (ref "LED52") (pin "A") (pinfunction "A_A") (pintype "passive"))
      (node (ref "LED63") (pin "A") (pinfunction "A_A") (pintype "passive"))
      (node (ref "LED74") (pin "A") (pinfunction "A_A") (pintype "passive"))
      (node (ref "LED8") (pin "A") (pinfunction "A_A") (pintype "passive"))
      (node (ref "LED85") (pin "A") (pinfunction "A_A") (pintype "passive"))
      (node (ref "LED96") (pin "A") (pinfunction "A_A") (pintype "passive"))
      (node (ref "Q8") (pin "E") (pinfunction "E_E") (pintype "passive"))
    )
    (net (code "33") (name "/COLUMNA_ANODOS_9") (class "Default")
      (node (ref "LED108") (pin "A") (pinfunction "A_A") (pintype "passive"))
      (node (ref "LED31") (pin "A") (pinfunction "A_A") (pintype "passive"))
      (node (ref "LED42") (pin "A") (pinfunction "A_A") (pintype "passive"))
      (node (ref "LED53") (pin "A") (pinfunction "A_A") (pintype "passive"))
      (node (ref "LED64") (pin "A") (pinfunction "A_A") (pintype "passive"))
      (node (ref "LED75") (pin "A") (pinfunction "A_A") (pintype "passive"))
      (node (ref "LED86") (pin "A") (pinfunction "A_A") (pintype "passive"))
      (node (ref "LED9") (pin "A") (pinfunction "A_A") (pintype "passive"))
      (node (ref "LED97") (pin "A") (pinfunction "A_A") (pintype "passive"))
      (node (ref "Q9") (pin "E") (pinfunction "E_E") (pintype "passive"))
    )
    (net (code "34") (name "/COLUMNA_ANODOS_10") (class "Default")
      (node (ref "LED10") (pin "A") (pinfunction "A_A") (pintype "passive"))
      (node (ref "LED109") (pin "A") (pinfunction "A_A") (pintype "passive"))
      (node (ref "LED32") (pin "A") (pinfunction "A_A") (pintype "passive"))
      (node (ref "LED43") (pin "A") (pinfunction "A_A") (pintype "passive"))
      (node (ref "LED65") (pin "A") (pinfunction "A_A") (pintype "passive"))
      (node (ref "LED76") (pin "A") (pinfunction "A_A") (pintype "passive"))
      (node (ref "LED87") (pin "A") (pinfunction "A_A") (pintype "passive"))
      (node (ref "LED98") (pin "A") (pinfunction "A_A") (pintype "passive"))
      (node (ref "Q10") (pin "E") (pinfunction "E_E") (pintype "passive"))
    )
    (net (code "35") (name "/COLUMNA_ANODOS_11") (class "Default")
      (node (ref "LED11") (pin "A") (pinfunction "A_A") (pintype "passive"))
      (node (ref "LED110") (pin "A") (pinfunction "A_A") (pintype "passive"))
      (node (ref "LED33") (pin "A") (pinfunction "A_A") (pintype "passive"))
      (node (ref "LED66") (pin "A") (pinfunction "A_A") (pintype "passive"))
      (node (ref "LED77") (pin "A") (pinfunction "A_A") (pintype "passive"))
      (node (ref "LED88") (pin "A") (pinfunction "A_A") (pintype "passive"))
      (node (ref "LED99") (pin "A") (pinfunction "A_A") (pintype "passive"))
      (node (ref "Q11") (pin "E") (pinfunction "E_E") (pintype "passive"))
    )
    (net (code "36") (name "/FILA_CATODOS_1") (class "Default")
      (node (ref "LED1") (pin "K") (pinfunction "C_K") (pintype "passive"))
      (node (ref "LED10") (pin "K") (pinfunction "C_K") (pintype "passive"))
      (node (ref "LED11") (pin "K") (pinfunction "C_K") (pintype "passive"))
      (node (ref "LED2") (pin "K") (pinfunction "C_K") (pintype "passive"))
      (node (ref "LED3") (pin "K") (pinfunction "C_K") (pintype "passive"))
      (node (ref "LED4") (pin "K") (pinfunction "C_K") (pintype "passive"))
      (node (ref "LED6") (pin "K") (pinfunction "C_K") (pintype "passive"))
      (node (ref "LED7") (pin "K") (pinfunction "C_K") (pintype "passive"))
      (node (ref "LED8") (pin "K") (pinfunction "C_K") (pintype "passive"))
      (node (ref "LED9") (pin "K") (pinfunction "C_K") (pintype "passive"))
      (node (ref "Q12") (pin "C") (pinfunction "C_C") (pintype "passive"))
    )
    (net (code "37") (name "/FILA_CATODOS_2") (class "Default")
      (node (ref "LED12") (pin "K") (pinfunction "C_K") (pintype "passive"))
      (node (ref "LED13") (pin "K") (pinfunction "C_K") (pintype "passive"))
      (node (ref "LED14") (pin "K") (pinfunction "C_K") (pintype "passive"))
      (node (ref "LED16") (pin "K") (pinfunction "C_K") (pintype "passive"))
      (node (ref "LED17") (pin "K") (pinfunction "C_K") (pintype "passive"))
      (node (ref "LED18") (pin "K") (pinfunction "C_K") (pintype "passive"))
      (node (ref "LED19") (pin "K") (pinfunction "C_K") (pintype "passive"))
      (node (ref "Q13") (pin "C") (pinfunction "C_C") (pintype "passive"))
    )
    (net (code "38") (name "/FILA_CATODOS_3") (class "Default")
      (node (ref "LED23") (pin "K") (pinfunction "C_K") (pintype "passive"))
      (node (ref "LED24") (pin "K") (pinfunction "C_K") (pintype "passive"))
      (node (ref "LED25") (pin "K") (pinfunction "C_K") (pintype "passive"))
      (node (ref "LED26") (pin "K") (pinfunction "C_K") (pintype "passive"))
      (node (ref "LED27") (pin "K") (pinfunction "C_K") (pintype "passive"))
      (node (ref "LED28") (pin "K") (pinfunction "C_K") (pintype "passive"))
      (node (ref "LED29") (pin "K") (pinfunction "C_K") (pintype "passive"))
      (node (ref "LED30") (pin "K") (pinfunction "C_K") (pintype "passive"))
      (node (ref "LED31") (pin "K") (pinfunction "C_K") (pintype "passive"))
      (node (ref "LED32") (pin "K") (pinfunction "C_K") (pintype "passive"))
      (node (ref "LED33") (pin "K") (pinfunction "C_K") (pintype "passive"))
      (node (ref "Q14") (pin "C") (pinfunction "C_C") (pintype "passive"))
    )
    (net (code "39") (name "/FILA_CATODOS_4") (class "Default")
      (node (ref "LED34") (pin "K") (pinfunction "C_K") (pintype "passive"))
      (node (ref "LED35") (pin "K") (pinfunction "C_K") (pintype "passive"))
      (node (ref "LED36") (pin "K") (pinfunction "C_K") (pintype "passive"))
      (node (ref "LED37") (pin "K") (pinfunction "C_K") (pintype "passive"))
      (node (ref "LED39") (pin "K") (pinfunction "C_K") (pintype "passive"))
      (node (ref "LED40") (pin "K") (pinfunction "C_K") (pintype "passive"))
      (node (ref "LED41") (pin "K") (pinfunction "C_K") (pintype "passive"))
      (node (ref "LED42") (pin "K") (pinfunction "C_K") (pintype "passive"))
      (node (ref "LED43") (pin "K") (pinfunction "C_K") (pintype "passive"))
      (node (ref "Q15") (pin "C") (pinfunction "C_C") (pintype "passive"))
    )
    (net (code "40") (name "/FILA_CATODOS_5") (class "Default")
      (node (ref "LED45") (pin "K") (pinfunction "C_K") (pintype "passive"))
      (node (ref "LED46") (pin "K") (pinfunction "C_K") (pintype "passive"))
      (node (ref "LED47") (pin "K") (pinfunction "C_K") (pintype "passive"))
      (node (ref "LED48") (pin "K") (pinfunction "C_K") (pintype "passive"))
      (node (ref "LED49") (pin "K") (pinfunction "C_K") (pintype "passive"))
      (node (ref "LED50") (pin "K") (pinfunction "C_K") (pintype "passive"))
      (node (ref "LED51") (pin "K") (pinfunction "C_K") (pintype "passive"))
      (node (ref "LED52") (pin "K") (pinfunction "C_K") (pintype "passive"))
      (node (ref "LED53") (pin "K") (pinfunction "C_K") (pintype "passive"))
      (node (ref "Q16") (pin "C") (pinfunction "C_C") (pintype "passive"))
    )
    (net (code "41") (name "/FILA_CATODOS_6") (class "Default")
      (node (ref "LED58") (pin "K") (pinfunction "C_K") (pintype "passive"))
      (node (ref "LED59") (pin "K") (pinfunction "C_K") (pintype "passive"))
      (node (ref "LED60") (pin "K") (pinfunction "C_K") (pintype "passive"))
      (node (ref "LED61") (pin "K") (pinfunction "C_K") (pintype "passive"))
      (node (ref "LED63") (pin "K") (pinfunction "C_K") (pintype "passive"))
      (node (ref "LED64") (pin "K") (pinfunction "C_K") (pintype "passive"))
      (node (ref "LED65") (pin "K") (pinfunction "C_K") (pintype "passive"))
      (node (ref "LED66") (pin "K") (pinfunction "C_K") (pintype "passive"))
      (node (ref "Q17") (pin "C") (pinfunction "C_C") (pintype "passive"))
    )
    (net (code "42") (name "/FILA_CATODOS_7") (class "Default")
      (node (ref "LED67") (pin "K") (pinfunction "C_K") (pintype "passive"))
      (node (ref "LED68") (pin "K") (pinfunction "C_K") (pintype "passive"))
      (node (ref "LED69") (pin "K") (pinfunction "C_K") (pintype "passive"))
      (node (ref "LED70") (pin "K") (pinfunction "C_K") (pintype "passive"))
      (node (ref "LED72") (pin "K") (pinfunction "C_K") (pintype "passive"))
      (node (ref "LED73") (pin "K") (pinfunction "C_K") (pintype "passive"))
      (node (ref "LED74") (pin "K") (pinfunction "C_K") (pintype "passive"))
      (node (ref "LED75") (pin "K") (pinfunction "C_K") (pintype "passive"))
      (node (ref "LED76") (pin "K") (pinfunction "C_K") (pintype "passive"))
      (node (ref "LED77") (pin "K") (pinfunction "C_K") (pintype "passive"))
      (node (ref "Q18") (pin "C") (pinfunction "C_C") (pintype "passive"))
    )
    (net (code "43") (name "/FILA_CATODOS_8") (class "Default")
      (node (ref "LED79") (pin "K") (pinfunction "C_K") (pintype "passive"))
      (node (ref "LED80") (pin "K") (pinfunction "C_K") (pintype "passive"))
      (node (ref "LED81") (pin "K") (pinfunction "C_K") (pintype "passive"))
      (node (ref "LED82") (pin "K") (pinfunction "C_K") (pintype "passive"))
      (node (ref "LED83") (pin "K") (pinfunction "C_K") (pintype "passive"))
      (node (ref "LED84") (pin "K") (pinfunction "C_K") (pintype "passive"))
      (node (ref "LED85") (pin "K") (pinfunction "C_K") (pintype "passive"))
      (node (ref "LED86") (pin "K") (pinfunction "C_K") (pintype "passive"))
      (node (ref "LED87") (pin "K") (pinfunction "C_K") (pintype "passive"))
      (node (ref "LED88") (pin "K") (pinfunction "C_K") (pintype "passive"))
      (node (ref "Q19") (pin "C") (pinfunction "C_C") (pintype "passive"))
    )
    (net (code "44") (name "/FILA_CATODOS_9") (class "Default")
      (node (ref "LED89") (pin "K") (pinfunction "C_K") (pintype "passive"))
      (node (ref "LED90") (pin "K") (pinfunction "C_K") (pintype "passive"))
      (node (ref "LED91") (pin "K") (pinfunction "C_K") (pintype "passive"))
      (node (ref "LED92") (pin "K") (pinfunction "C_K") (pintype "passive"))
      (node (ref "LED93") (pin "K") (pinfunction "C_K") (pintype "passive"))
      (node (ref "LED94") (pin "K") (pinfunction "C_K") (pintype "passive"))
      (node (ref "LED95") (pin "K") (pinfunction "C_K") (pintype "passive"))
      (node (ref "LED96") (pin "K") (pinfunction "C_K") (pintype "passive"))
      (node (ref "LED97") (pin "K") (pinfunction "C_K") (pintype "passive"))
      (node (ref "LED98") (pin "K") (pinfunction "C_K") (pintype "passive"))
      (node (ref "LED99") (pin "K") (pinfunction "C_K") (pintype "passive"))
      (node (ref "Q20") (pin "C") (pinfunction "C_C") (pintype "passive"))
    )
    (net (code "45") (name "/FILA_CATODOS_10") (class "Default")
      (node (ref "LED100") (pin "K") (pinfunction "C_K") (pintype "passive"))
      (node (ref "LED101") (pin "K") (pinfunction "C_K") (pintype "passive"))
      (node (ref "LED102") (pin "K") (pinfunction "C_K") (pintype "passive"))
      (node (ref "LED103") (pin "K") (pinfunction "C_K") (pintype "passive"))
      (node (ref "LED104") (pin "K") (pinfunction "C_K") (pintype "passive"))
      (node (ref "LED105") (pin "K") (pinfunction "C_K") (pintype "passive"))
      (node (ref "LED106") (pin "K") (pinfunction "C_K") (pintype "passive"))
      (node (ref "LED107") (pin "K") (pinfunction "C_K") (pintype "passive"))
      (node (ref "LED108") (pin "K") (pinfunction "C_K") (pintype "passive"))
      (node (ref "LED109") (pin "K") (pinfunction "C_K") (pintype "passive"))
      (node (ref "LED110") (pin "K") (pinfunction "C_K") (pintype "passive"))
      (node (ref "Q21") (pin "C") (pinfunction "C_C") (pintype "passive"))
    )
    (net (code "46") (name "/PULSADOR_SET") (class "Default")
      (node (ref "IC1") (pin "21") (pinfunction "INT/RB0_21") (pintype "bidirectional"))
      (node (ref "PULSADOR") (pin "2") (pinfunction "2_2") (pintype "passive"))
      (node (ref "R34") (pin "2") (pinfunction "2_2") (pintype "passive"))
    )
    (net (code "47") (name "GNDA") (class "Default")
      (node (ref "C1") (pin "-") (pinfunction "-_-") (pintype "passive"))
      (node (ref "C4") (pin "2") (pinfunction "2_2") (pintype "passive"))
      (node (ref "C5") (pin "2") (pinfunction "2_2") (pintype "passive"))
      (node (ref "IC1") (pin "19") (pinfunction "VSS_19") (pintype "power_in"))
      (node (ref "IC1") (pin "8") (pinfunction "VSS_8") (pintype "power_in"))
      (node (ref "IC2") (pin "2") (pinfunction "GND_2") (pintype "passive"))
      (node (ref "JP1") (pin "1") (pinfunction "1_1") (pintype "passive"))
      (node (ref "PULSADOR") (pin "1") (pinfunction "1_1") (pintype "passive"))
      (node (ref "Q12") (pin "E") (pinfunction "E_E") (pintype "passive"))
      (node (ref "Q13") (pin "E") (pinfunction "E_E") (pintype "passive"))
      (node (ref "Q14") (pin "E") (pinfunction "E_E") (pintype "passive"))
      (node (ref "Q15") (pin "E") (pinfunction "E_E") (pintype "passive"))
      (node (ref "Q16") (pin "E") (pinfunction "E_E") (pintype "passive"))
      (node (ref "Q17") (pin "E") (pinfunction "E_E") (pintype "passive"))
      (node (ref "Q18") (pin "E") (pinfunction "E_E") (pintype "passive"))
      (node (ref "Q19") (pin "E") (pinfunction "E_E") (pintype "passive"))
      (node (ref "Q20") (pin "E") (pinfunction "E_E") (pintype "passive"))
      (node (ref "Q21") (pin "E") (pinfunction "E_E") (pintype "passive"))
    )
    (net (code "48") (name "Net-(D1-PadA)") (class "Default")
      (node (ref "D1") (pin "A") (pinfunction "A_A") (pintype "passive"))
      (node (ref "R33") (pin "2") (pinfunction "2_2") (pintype "passive"))
    )
    (net (code "49") (name "Net-(D2-PadA)") (class "Default")
      (node (ref "D2") (pin "A") (pinfunction "A_A") (pintype "passive"))
      (node (ref "JP1") (pin "2") (pinfunction "2_2") (pintype "passive"))
    )
    (net (code "50") (name "Net-(IC1-OSC1{slash}CLKIN)") (class "Default")
      (node (ref "C4") (pin "1") (pinfunction "1_1") (pintype "passive"))
      (node (ref "IC1") (pin "9") (pinfunction "OSC1/CLKIN_9") (pintype "input"))
      (node (ref "Q22") (pin "2") (pinfunction "2_2") (pintype "passive"))
    )
    (net (code "51") (name "Net-(IC1-OSC2{slash}CLKOUT)") (class "Default")
      (node (ref "C5") (pin "1") (pinfunction "1_1") (pintype "passive"))
      (node (ref "IC1") (pin "10") (pinfunction "OSC2/CLKOUT_10") (pintype "output"))
      (node (ref "Q22") (pin "1") (pinfunction "1_1") (pintype "passive"))
    )
    (net (code "52") (name "Net-(IC1-~{MCLR{slash}THV})") (class "Default")
      (node (ref "D1") (pin "C") (pinfunction "C_C") (pintype "passive"))
      (node (ref "IC1") (pin "1") (pinfunction "~{MCLR/THV}_1") (pintype "input"))
    )
    (net (code "53") (name "Net-(IC2-VI)") (class "Default")
      (node (ref "D2") (pin "C") (pinfunction "C_C") (pintype "passive"))
      (node (ref "IC2") (pin "1") (pinfunction "VI_1") (pintype "input"))
    )
    (net (code "54") (name "Net-(Q1-PadB)") (class "Default")
      (node (ref "Q1") (pin "B") (pinfunction "B_B") (pintype "passive"))
      (node (ref "R1") (pin "2") (pinfunction "2_2") (pintype "passive"))
    )
    (net (code "55") (name "Net-(Q1-PadC)") (class "Default")
      (node (ref "Q1") (pin "C") (pinfunction "C_C") (pintype "passive"))
      (node (ref "R22") (pin "1") (pinfunction "1_1") (pintype "passive"))
    )
    (net (code "56") (name "Net-(Q2-PadB)") (class "Default")
      (node (ref "Q2") (pin "B") (pinfunction "B_B") (pintype "passive"))
      (node (ref "R2") (pin "2") (pinfunction "2_2") (pintype "passive"))
    )
    (net (code "57") (name "Net-(Q2-PadC)") (class "Default")
      (node (ref "Q2") (pin "C") (pinfunction "C_C") (pintype "passive"))
      (node (ref "R23") (pin "1") (pinfunction "1_1") (pintype "passive"))
    )
    (net (code "58") (name "Net-(Q3-PadB)") (class "Default")
      (node (ref "Q3") (pin "B") (pinfunction "B_B") (pintype "passive"))
      (node (ref "R3") (pin "2") (pinfunction "2_2") (pintype "passive"))
    )
    (net (code "59") (name "Net-(Q3-PadC)") (class "Default")
      (node (ref "Q3") (pin "C") (pinfunction "C_C") (pintype "passive"))
      (node (ref "R24") (pin "1") (pinfunction "1_1") (pintype "passive"))
    )
    (net (code "60") (name "Net-(Q4-PadB)") (class "Default")
      (node (ref "Q4") (pin "B") (pinfunction "B_B") (pintype "passive"))
      (node (ref "R4") (pin "2") (pinfunction "2_2") (pintype "passive"))
    )
    (net (code "61") (name "Net-(Q4-PadC)") (class "Default")
      (node (ref "Q4") (pin "C") (pinfunction "C_C") (pintype "passive"))
      (node (ref "R25") (pin "1") (pinfunction "1_1") (pintype "passive"))
    )
    (net (code "62") (name "Net-(Q5-PadB)") (class "Default")
      (node (ref "Q5") (pin "B") (pinfunction "B_B") (pintype "passive"))
      (node (ref "R5") (pin "2") (pinfunction "2_2") (pintype "passive"))
    )
    (net (code "63") (name "Net-(Q5-PadC)") (class "Default")
      (node (ref "Q5") (pin "C") (pinfunction "C_C") (pintype "passive"))
      (node (ref "R26") (pin "1") (pinfunction "1_1") (pintype "passive"))
    )
    (net (code "64") (name "Net-(Q6-PadB)") (class "Default")
      (node (ref "Q6") (pin "B") (pinfunction "B_B") (pintype "passive"))
      (node (ref "R6") (pin "2") (pinfunction "2_2") (pintype "passive"))
    )
    (net (code "65") (name "Net-(Q6-PadC)") (class "Default")
      (node (ref "Q6") (pin "C") (pinfunction "C_C") (pintype "passive"))
      (node (ref "R27") (pin "1") (pinfunction "1_1") (pintype "passive"))
    )
    (net (code "66") (name "Net-(Q7-PadB)") (class "Default")
      (node (ref "Q7") (pin "B") (pinfunction "B_B") (pintype "passive"))
      (node (ref "R7") (pin "2") (pinfunction "2_2") (pintype "passive"))
    )
    (net (code "67") (name "Net-(Q7-PadC)") (class "Default")
      (node (ref "Q7") (pin "C") (pinfunction "C_C") (pintype "passive"))
      (node (ref "R28") (pin "1") (pinfunction "1_1") (pintype "passive"))
    )
    (net (code "68") (name "Net-(Q8-PadB)") (class "Default")
      (node (ref "Q8") (pin "B") (pinfunction "B_B") (pintype "passive"))
      (node (ref "R8") (pin "2") (pinfunction "2_2") (pintype "passive"))
    )
    (net (code "69") (name "Net-(Q8-PadC)") (class "Default")
      (node (ref "Q8") (pin "C") (pinfunction "C_C") (pintype "passive"))
      (node (ref "R29") (pin "1") (pinfunction "1_1") (pintype "passive"))
    )
    (net (code "70") (name "Net-(Q9-PadB)") (class "Default")
      (node (ref "Q9") (pin "B") (pinfunction "B_B") (pintype "passive"))
      (node (ref "R9") (pin "2") (pinfunction "2_2") (pintype "passive"))
    )
    (net (code "71") (name "Net-(Q9-PadC)") (class "Default")
      (node (ref "Q9") (pin "C") (pinfunction "C_C") (pintype "passive"))
      (node (ref "R30") (pin "1") (pinfunction "1_1") (pintype "passive"))
    )
    (net (code "72") (name "Net-(Q10-PadB)") (class "Default")
      (node (ref "Q10") (pin "B") (pinfunction "B_B") (pintype "passive"))
      (node (ref "R10") (pin "2") (pinfunction "2_2") (pintype "passive"))
    )
    (net (code "73") (name "Net-(Q10-PadC)") (class "Default")
      (node (ref "Q10") (pin "C") (pinfunction "C_C") (pintype "passive"))
      (node (ref "R31") (pin "1") (pinfunction "1_1") (pintype "passive"))
    )
    (net (code "74") (name "Net-(Q11-PadB)") (class "Default")
      (node (ref "Q11") (pin "B") (pinfunction "B_B") (pintype "passive"))
      (node (ref "R11") (pin "2") (pinfunction "2_2") (pintype "passive"))
    )
    (net (code "75") (name "Net-(Q11-PadC)") (class "Default")
      (node (ref "Q11") (pin "C") (pinfunction "C_C") (pintype "passive"))
      (node (ref "R32") (pin "1") (pinfunction "1_1") (pintype "passive"))
    )
    (net (code "76") (name "Net-(Q12-PadB)") (class "Default")
      (node (ref "Q12") (pin "B") (pinfunction "B_B") (pintype "passive"))
      (node (ref "R12") (pin "2") (pinfunction "2_2") (pintype "passive"))
    )
    (net (code "77") (name "Net-(Q13-PadB)") (class "Default")
      (node (ref "Q13") (pin "B") (pinfunction "B_B") (pintype "passive"))
      (node (ref "R13") (pin "2") (pinfunction "2_2") (pintype "passive"))
    )
    (net (code "78") (name "Net-(Q14-PadB)") (class "Default")
      (node (ref "Q14") (pin "B") (pinfunction "B_B") (pintype "passive"))
      (node (ref "R14") (pin "2") (pinfunction "2_2") (pintype "passive"))
    )
    (net (code "79") (name "Net-(Q15-PadB)") (class "Default")
      (node (ref "Q15") (pin "B") (pinfunction "B_B") (pintype "passive"))
      (node (ref "R15") (pin "2") (pinfunction "2_2") (pintype "passive"))
    )
    (net (code "80") (name "Net-(Q16-PadB)") (class "Default")
      (node (ref "Q16") (pin "B") (pinfunction "B_B") (pintype "passive"))
      (node (ref "R16") (pin "2") (pinfunction "2_2") (pintype "passive"))
    )
    (net (code "81") (name "Net-(Q17-PadB)") (class "Default")
      (node (ref "Q17") (pin "B") (pinfunction "B_B") (pintype "passive"))
      (node (ref "R17") (pin "2") (pinfunction "2_2") (pintype "passive"))
    )
    (net (code "82") (name "Net-(Q18-PadB)") (class "Default")
      (node (ref "Q18") (pin "B") (pinfunction "B_B") (pintype "passive"))
      (node (ref "R18") (pin "2") (pinfunction "2_2") (pintype "passive"))
    )
    (net (code "83") (name "Net-(Q19-PadB)") (class "Default")
      (node (ref "Q19") (pin "B") (pinfunction "B_B") (pintype "passive"))
      (node (ref "R19") (pin "2") (pinfunction "2_2") (pintype "passive"))
    )
    (net (code "84") (name "Net-(Q20-PadB)") (class "Default")
      (node (ref "Q20") (pin "B") (pinfunction "B_B") (pintype "passive"))
      (node (ref "R20") (pin "2") (pinfunction "2_2") (pintype "passive"))
    )
    (net (code "85") (name "Net-(Q21-PadB)") (class "Default")
      (node (ref "Q21") (pin "B") (pinfunction "B_B") (pintype "passive"))
      (node (ref "R21") (pin "2") (pinfunction "2_2") (pintype "passive"))
    )
  )
)
